# SCH_Controller-12-volt-power_EasyEDA.net
KiCad netlist of a schematic drawn in EasyEDA
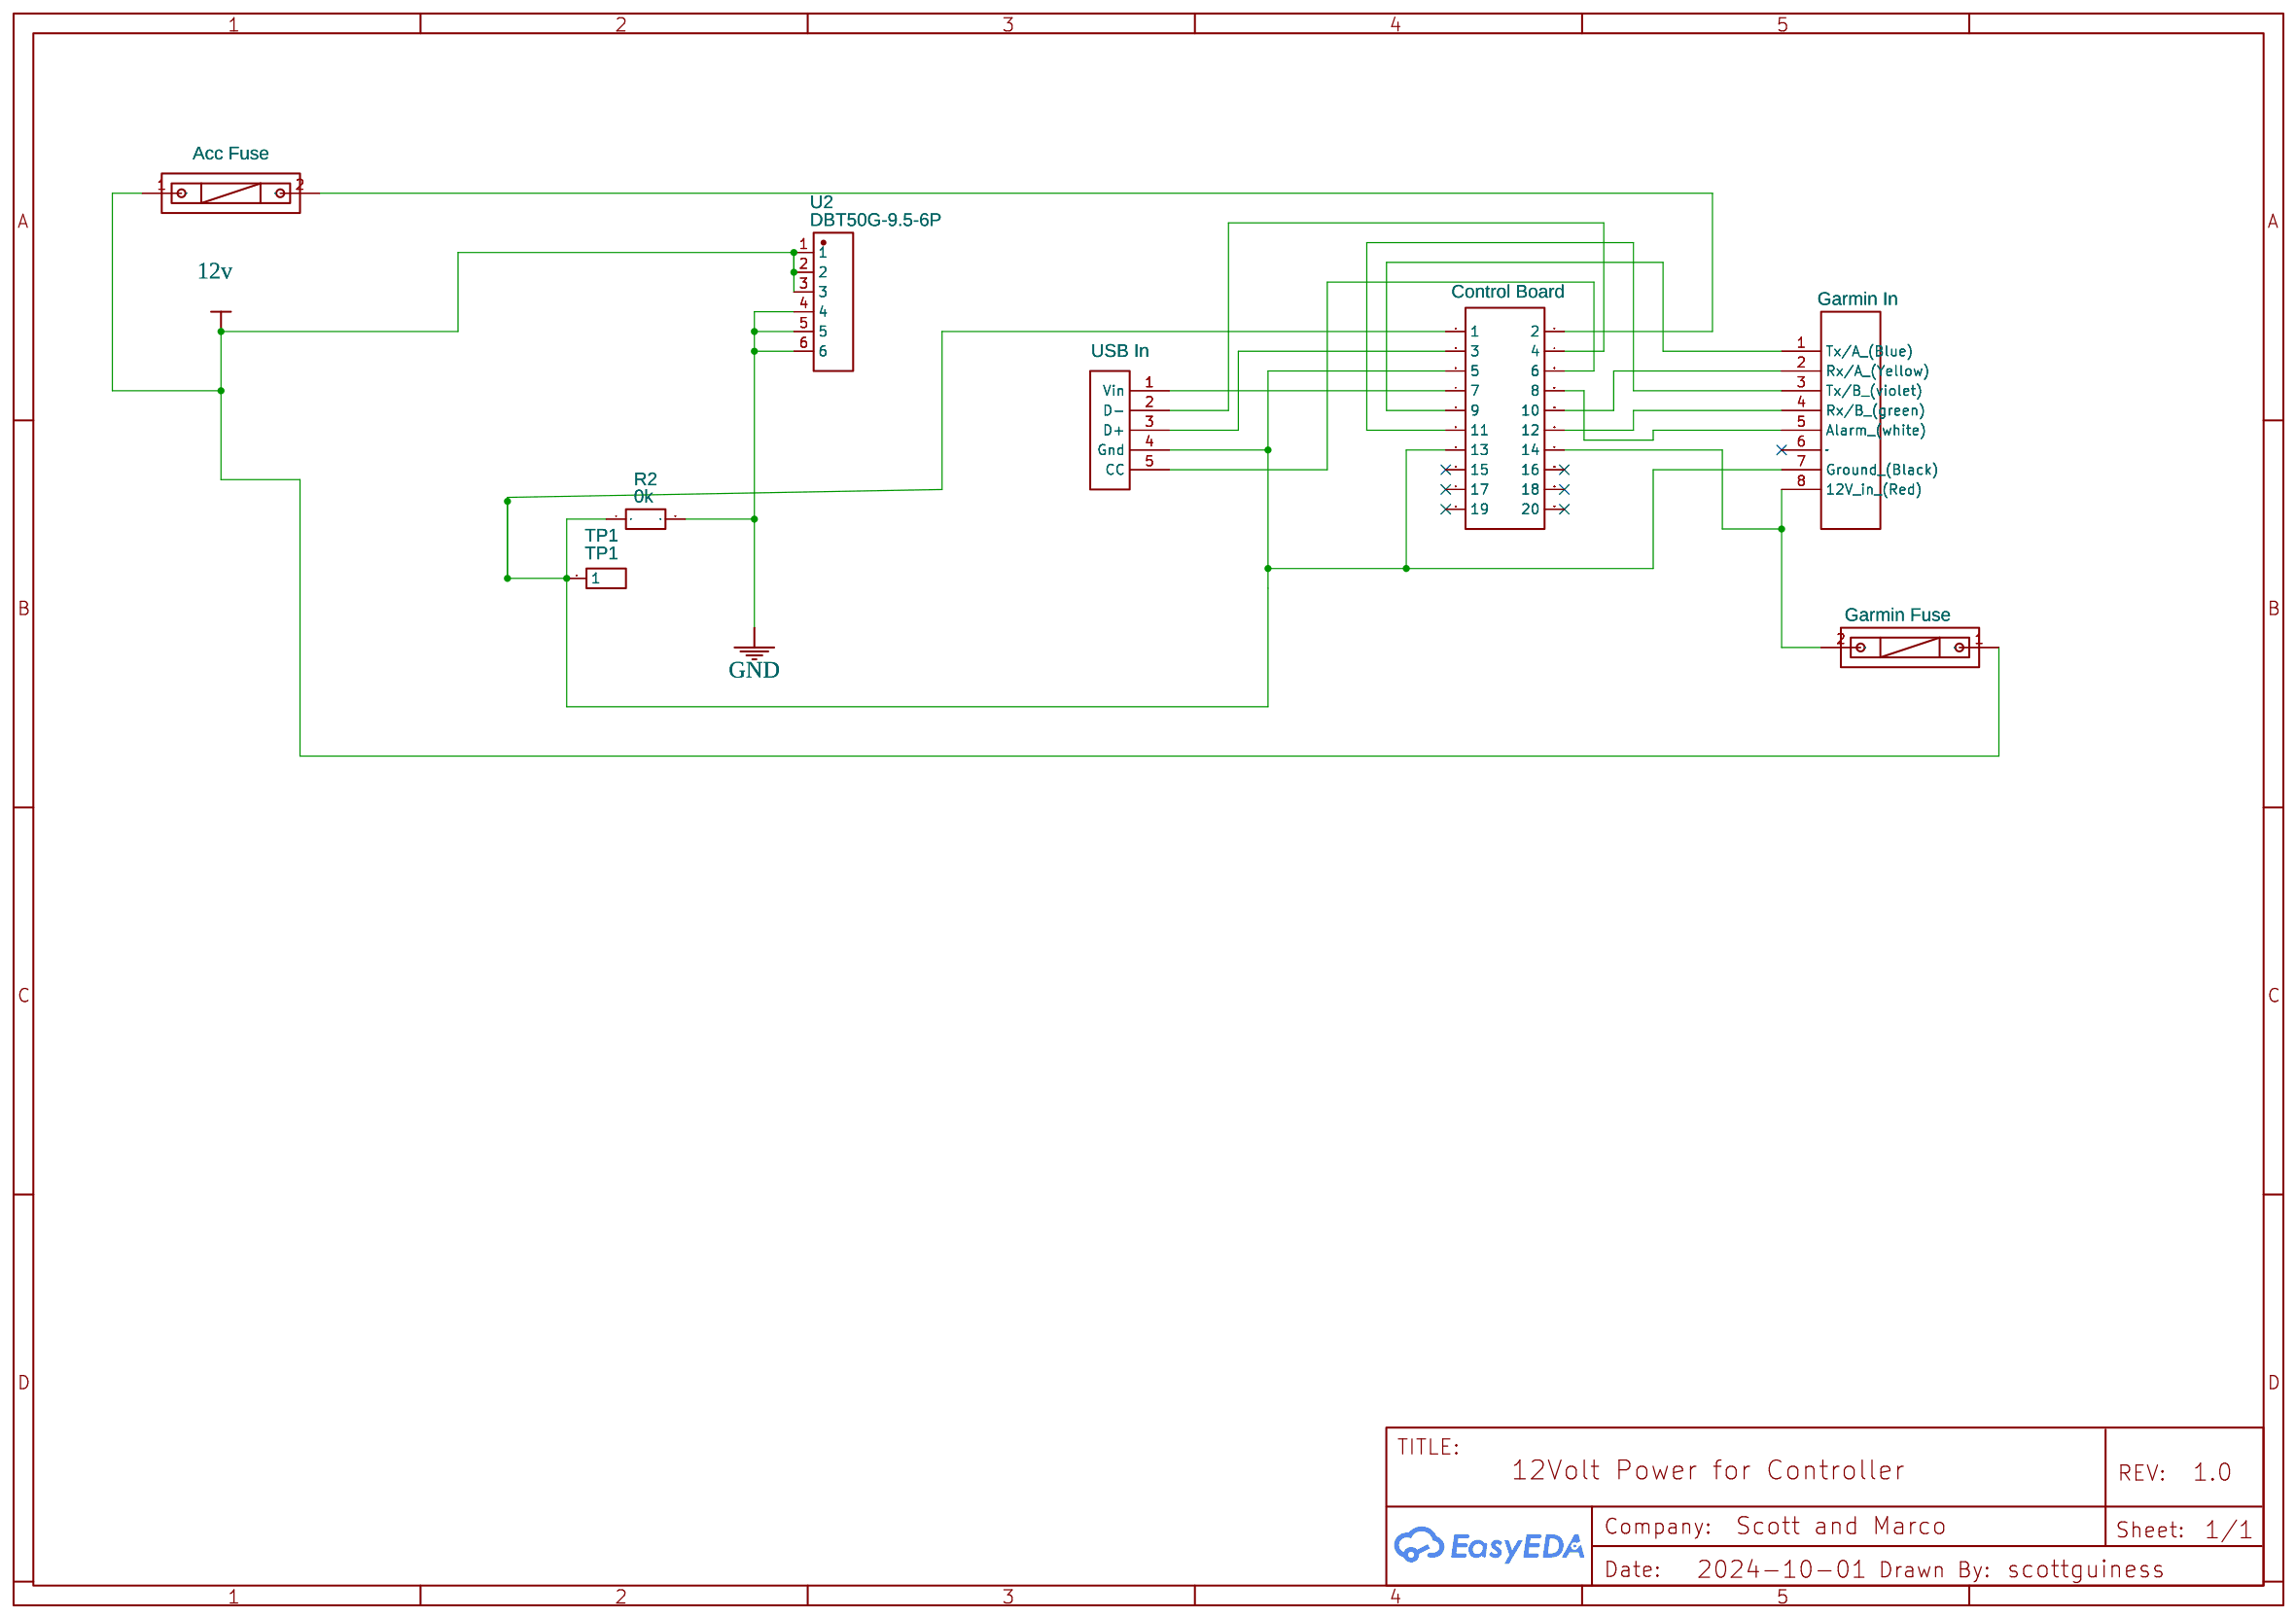
[diagram p0: schematic sheet]

(export (version "E")
  (design (tool "Eeschema 10.0.6"))
  (components
    (comp (ref "ACC-FUSE-5X20=BLX-ATYPE-FUSE-HOLDER")
      (value "Acc Fuse")
      (fields
        (field (name "Manufacturer Part") "5x20 BLX-A型 保险丝支架 XC-7")
        (field (name "Manufacturer") "xcfuse(旭程)")
      )
      (libsource (lib "") (part "5x20 BLX-Atype Fuse holder XC-7"))
    )
    (comp (ref "BUTTON_LED1") (value "Control Board") (libsource (lib "") (part "HDR-M-2.54_2x10")))
    (comp (ref "GARMIN-FUSE-5X20-BLX-ATYPE-FUSE-HOLDER")
      (value "Garmin Fuse")
      (fields
        (field (name "Manufacturer Part") "5x20 BLX-A型 保险丝支架 XC-7")
        (field (name "Manufacturer") "xcfuse(旭程)")
      )
      (libsource (lib "") (part "5x20 BLX-Atype Fuse holder XC-7_1"))
    )
    (comp (ref "GARMIN-GPS")
      (value "Garmin In")
      (fields (field (name "Manufacturer") "Waveshare"))
      (libsource (lib "") (part "8PIN JST CONNECTOR"))
    )
    (comp (ref "R2") (value "0k") (libsource (lib "") (part "R_AXIAL-0.3_EU")))
    (comp (ref "TP1") (value "TP1") (libsource (lib "") (part "HDR-M-2.54_1x1")))
    (comp (ref "U2")
      (value "DBT50G-9.5-6P")
      (fields
        (field (name "Manufacturer Part") "DBT50G-9.5-6P-BK-P OGC")
        (field (name "Manufacturer") "DORABO(地博电气)")
      )
      (libsource (lib "") (part "DBT50G-9.5-6P"))
    )
    (comp (ref "USB-C") (value "USB In") (libsource (lib "") (part "JST XH 1x5")))
  )
  (nets
    (net (code "1") (name "12v") (class "Default")
      (node (ref "ACC-FUSE-5X20=BLX-ATYPE-FUSE-HOLDER") (pin "1") (pinfunction "1_1") (pintype "unspecified"))
      (node (ref "GARMIN-FUSE-5X20-BLX-ATYPE-FUSE-HOLDER") (pin "1") (pinfunction "1_1") (pintype "unspecified"))
      (node (ref "U2") (pin "1") (pinfunction "1_1") (pintype "unspecified"))
      (node (ref "U2") (pin "2") (pinfunction "2_2") (pintype "unspecified"))
      (node (ref "U2") (pin "3") (pinfunction "3_3") (pintype "unspecified"))
    )
    (net (code "2") (name "GND") (class "Default")
      (node (ref "R2") (pin "2") (pinfunction "2_2") (pintype "unspecified"))
      (node (ref "U2") (pin "4") (pinfunction "4_4") (pintype "unspecified"))
      (node (ref "U2") (pin "5") (pinfunction "5_5") (pintype "unspecified"))
      (node (ref "U2") (pin "6") (pinfunction "6_6") (pintype "unspecified"))
    )
    (net (code "3") (name "Net-(ACC-FUSE-5X20=BLX-ATYPE-FUSE-HOLDER-Pad2)") (class "Default")
      (node (ref "ACC-FUSE-5X20=BLX-ATYPE-FUSE-HOLDER") (pin "2") (pinfunction "2_2") (pintype "unspecified"))
      (node (ref "BUTTON_LED1") (pin "2") (pinfunction "2_2") (pintype "unspecified"))
    )
    (net (code "4") (name "Net-(GARMIN-GPS-12V_in_(Red))") (class "Default")
      (node (ref "BUTTON_LED1") (pin "14") (pinfunction "14_14") (pintype "unspecified"))
      (node (ref "GARMIN-FUSE-5X20-BLX-ATYPE-FUSE-HOLDER") (pin "2") (pinfunction "2_2") (pintype "unspecified"))
      (node (ref "GARMIN-GPS") (pin "8") (pinfunction "12V_in_(Red)_8") (pintype "unspecified"))
    )
    (net (code "5") (name "Net-(GARMIN-GPS-Alarm_(white))") (class "Default")
      (node (ref "BUTTON_LED1") (pin "8") (pinfunction "8_8") (pintype "unspecified"))
      (node (ref "GARMIN-GPS") (pin "5") (pinfunction "Alarm_(white)_5") (pintype "unspecified"))
    )
    (net (code "6") (name "Net-(GARMIN-GPS-Ground_(Black))") (class "Default")
      (node (ref "BUTTON_LED1") (pin "1") (pinfunction "1_1") (pintype "unspecified"))
      (node (ref "BUTTON_LED1") (pin "13") (pinfunction "13_13") (pintype "unspecified"))
      (node (ref "BUTTON_LED1") (pin "5") (pinfunction "5_5") (pintype "unspecified"))
      (node (ref "GARMIN-GPS") (pin "7") (pinfunction "Ground_(Black)_7") (pintype "unspecified"))
      (node (ref "R2") (pin "1") (pinfunction "1_1") (pintype "unspecified"))
      (node (ref "TP1") (pin "1") (pinfunction "1_1") (pintype "input"))
      (node (ref "USB-C") (pin "4") (pinfunction "Gnd_4") (pintype "unspecified"))
    )
    (net (code "7") (name "Net-(GARMIN-GPS-Rx{slash}A_(Yellow))") (class "Default")
      (node (ref "BUTTON_LED1") (pin "10") (pinfunction "10_10") (pintype "unspecified"))
      (node (ref "GARMIN-GPS") (pin "2") (pinfunction "Rx/A_(Yellow)_2") (pintype "unspecified"))
    )
    (net (code "8") (name "Net-(GARMIN-GPS-Rx{slash}B_(green))") (class "Default")
      (node (ref "BUTTON_LED1") (pin "12") (pinfunction "12_12") (pintype "unspecified"))
      (node (ref "GARMIN-GPS") (pin "4") (pinfunction "Rx/B_(green)_4") (pintype "unspecified"))
    )
    (net (code "9") (name "Net-(GARMIN-GPS-Tx{slash}A_(Blue))") (class "Default")
      (node (ref "BUTTON_LED1") (pin "9") (pinfunction "9_9") (pintype "unspecified"))
      (node (ref "GARMIN-GPS") (pin "1") (pinfunction "Tx/A_(Blue)_1") (pintype "unspecified"))
    )
    (net (code "10") (name "Net-(GARMIN-GPS-Tx{slash}B_(violet))") (class "Default")
      (node (ref "BUTTON_LED1") (pin "11") (pinfunction "11_11") (pintype "unspecified"))
      (node (ref "GARMIN-GPS") (pin "3") (pinfunction "Tx/B_(violet)_3") (pintype "unspecified"))
    )
    (net (code "11") (name "Net-(USB-C-CC)") (class "Default")
      (node (ref "BUTTON_LED1") (pin "6") (pinfunction "6_6") (pintype "unspecified"))
      (node (ref "USB-C") (pin "5") (pinfunction "CC_5") (pintype "unspecified"))
    )
    (net (code "12") (name "Net-(USB-C-D+)") (class "Default")
      (node (ref "BUTTON_LED1") (pin "3") (pinfunction "3_3") (pintype "unspecified"))
      (node (ref "USB-C") (pin "3") (pinfunction "D+_3") (pintype "unspecified"))
    )
    (net (code "13") (name "Net-(USB-C-D-)") (class "Default")
      (node (ref "BUTTON_LED1") (pin "4") (pinfunction "4_4") (pintype "unspecified"))
      (node (ref "USB-C") (pin "2") (pinfunction "D-_2") (pintype "unspecified"))
    )
    (net (code "14") (name "Net-(USB-C-Vin)") (class "Default")
      (node (ref "BUTTON_LED1") (pin "7") (pinfunction "7_7") (pintype "unspecified"))
      (node (ref "USB-C") (pin "1") (pinfunction "Vin_1") (pintype "unspecified"))
    )
    (net (code "15") (name "unconnected-(BUTTON_LED1-Pad15)") (class "Default")
      (node (ref "BUTTON_LED1") (pin "15") (pinfunction "15_15") (pintype "unspecified+no_connect"))
    )
    (net (code "16") (name "unconnected-(BUTTON_LED1-Pad16)") (class "Default")
      (node (ref "BUTTON_LED1") (pin "16") (pinfunction "16_16") (pintype "unspecified+no_connect"))
    )
    (net (code "17") (name "unconnected-(BUTTON_LED1-Pad17)") (class "Default")
      (node (ref "BUTTON_LED1") (pin "17") (pinfunction "17_17") (pintype "unspecified+no_connect"))
    )
    (net (code "18") (name "unconnected-(BUTTON_LED1-Pad18)") (class "Default")
      (node (ref "BUTTON_LED1") (pin "18") (pinfunction "18_18") (pintype "unspecified+no_connect"))
    )
    (net (code "19") (name "unconnected-(BUTTON_LED1-Pad19)") (class "Default")
      (node (ref "BUTTON_LED1") (pin "19") (pinfunction "19_19") (pintype "unspecified+no_connect"))
    )
    (net (code "20") (name "unconnected-(BUTTON_LED1-Pad20)") (class "Default")
      (node (ref "BUTTON_LED1") (pin "20") (pinfunction "20_20") (pintype "unspecified+no_connect"))
    )
    (net (code "21") (name "unconnected-(GARMIN-GPS-Accessory_On-Pad6)") (class "Default")
      (node (ref "GARMIN-GPS") (pin "6") (pinfunction "Accessory_On_6") (pintype "unspecified+no_connect"))
    )
  )
)
